# 00_CONNECTORS.net
KiCad netlist of a schematic drawn in Altium Designer
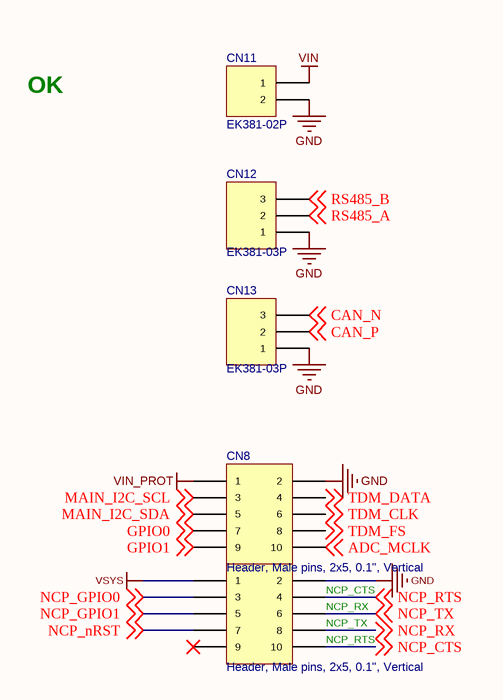
[diagram p0: 00_CONNECTORS.SchDoc]

(export (version "E")
  (design (tool "Eeschema 10.0.6"))
  (components
    (comp (ref "CN8")
      (value "Header, Male pins, 2x5, 0.1\", Vertical")
      (fields (field (name "MFG") "<GENERIC>") (field (name "FOOTPRINT CHECKED") "Assign OK, Footprint OK"))
      (libsource (lib "Miscellaneous Connectors") (part "Header 5X2"))
    )
    (comp (ref "CN9")
      (value "Header, Male pins, 2x5, 0.1\", Vertical")
      (fields (field (name "MFG") "<GENERIC>") (field (name "FOOTPRINT CHECKED") "Assign OK, Footprint OK"))
      (libsource (lib "Miscellaneous Connectors") (part "Header 5X2"))
    )
    (comp (ref "CN11")
      (value "EK381-02P")
      (footprint "EK381-02P")
      (description "Terminal block, 3.81mm, 2-Pin")
      (fields (field (name "MFG") "DINKLE") (field (name "FOOTPRINT CHECKED") "Assign OK, Footprint OK"))
      (libsource (lib "Miscellaneous Connectors") (part "Header 2"))
    )
    (comp (ref "CN12")
      (value "EK381-03P")
      (footprint "EK381-03P")
      (description "Terminal block, 3.81mm, 3-Pin")
      (fields (field (name "MFG") "DINKLE") (field (name "FOOTPRINT CHECKED") "Assign OK, Footprint OK"))
      (libsource (lib "Miscellaneous Connectors") (part "Header 3"))
    )
    (comp (ref "CN13")
      (value "EK381-03P")
      (footprint "EK381-03P")
      (description "Terminal block, 3.81mm, 3-Pin")
      (fields (field (name "MFG") "DINKLE") (field (name "FOOTPRINT CHECKED") "Assign OK, Footprint OK"))
      (libsource (lib "Miscellaneous Connectors") (part "Header 3"))
    )
  )
  (nets
    (net (code "1") (name "ADC_MCLK") (class "Default")
      (node (ref "CN8") (pin "10") (pinfunction "10_10") (pintype "passive"))
    )
    (net (code "2") (name "CAN_N") (class "Default")
      (node (ref "CN13") (pin "3L") (pinfunction "3_3L") (pintype "passive"))
    )
    (net (code "3") (name "CAN_P") (class "Default")
      (node (ref "CN13") (pin "2L") (pinfunction "2_2L") (pintype "passive"))
    )
    (net (code "4") (name "GND") (class "Default")
      (node (ref "CN11") (pin "2L") (pinfunction "2_2L") (pintype "passive"))
      (node (ref "CN12") (pin "1L") (pinfunction "1_1L") (pintype "passive"))
      (node (ref "CN13") (pin "1L") (pinfunction "1_1L") (pintype "passive"))
      (node (ref "CN8") (pin "2") (pinfunction "2_2") (pintype "passive"))
      (node (ref "CN9") (pin "2") (pinfunction "2_2") (pintype "passive"))
    )
    (net (code "5") (name "GPIO0") (class "Default")
      (node (ref "CN8") (pin "7") (pinfunction "7_7") (pintype "passive"))
    )
    (net (code "6") (name "GPIO1") (class "Default")
      (node (ref "CN8") (pin "9") (pinfunction "9_9") (pintype "passive"))
    )
    (net (code "7") (name "MAIN_I2C_SCL") (class "Default")
      (node (ref "CN8") (pin "3") (pinfunction "3_3") (pintype "passive"))
    )
    (net (code "8") (name "MAIN_I2C_SDA") (class "Default")
      (node (ref "CN8") (pin "5") (pinfunction "5_5") (pintype "passive"))
    )
    (net (code "9") (name "NCP_CTS") (class "Default")
      (node (ref "CN9") (pin "10") (pinfunction "10_10") (pintype "passive"))
    )
    (net (code "10") (name "NCP_GPIO0") (class "Default")
      (node (ref "CN9") (pin "3") (pinfunction "3_3") (pintype "passive"))
    )
    (net (code "11") (name "NCP_GPIO1") (class "Default")
      (node (ref "CN9") (pin "5") (pinfunction "5_5") (pintype "passive"))
    )
    (net (code "12") (name "NCP_RTS") (class "Default")
      (node (ref "CN9") (pin "4") (pinfunction "4_4") (pintype "passive"))
    )
    (net (code "13") (name "NCP_RX") (class "Default")
      (node (ref "CN9") (pin "8") (pinfunction "8_8") (pintype "passive"))
    )
    (net (code "14") (name "NCP_TX") (class "Default")
      (node (ref "CN9") (pin "6") (pinfunction "6_6") (pintype "passive"))
    )
    (net (code "15") (name "NCP_nRST") (class "Default")
      (node (ref "CN9") (pin "7") (pinfunction "7_7") (pintype "passive"))
    )
    (net (code "16") (name "RS485_A") (class "Default")
      (node (ref "CN12") (pin "2L") (pinfunction "2_2L") (pintype "passive"))
    )
    (net (code "17") (name "RS485_B") (class "Default")
      (node (ref "CN12") (pin "3L") (pinfunction "3_3L") (pintype "passive"))
    )
    (net (code "18") (name "TDM_CLK") (class "Default")
      (node (ref "CN8") (pin "6") (pinfunction "6_6") (pintype "passive"))
    )
    (net (code "19") (name "TDM_DATA") (class "Default")
      (node (ref "CN8") (pin "4") (pinfunction "4_4") (pintype "passive"))
    )
    (net (code "20") (name "TDM_FS") (class "Default")
      (node (ref "CN8") (pin "8") (pinfunction "8_8") (pintype "passive"))
    )
    (net (code "21") (name "VIN") (class "Default")
      (node (ref "CN11") (pin "1L") (pinfunction "1_1L") (pintype "passive"))
    )
    (net (code "22") (name "VIN_PROT") (class "Default")
      (node (ref "CN8") (pin "1") (pinfunction "1_1") (pintype "passive"))
    )
    (net (code "23") (name "VSYS") (class "Default")
      (node (ref "CN9") (pin "1") (pinfunction "1_1") (pintype "passive"))
    )
    (net (code "24") (name "unconnected-(CN9-Pad9)") (class "Default")
      (node (ref "CN9") (pin "9") (pinfunction "9_9") (pintype "passive+no_connect"))
    )
  )
)
